# Sheet1.net
KiCad netlist of a schematic drawn in Altium Designer
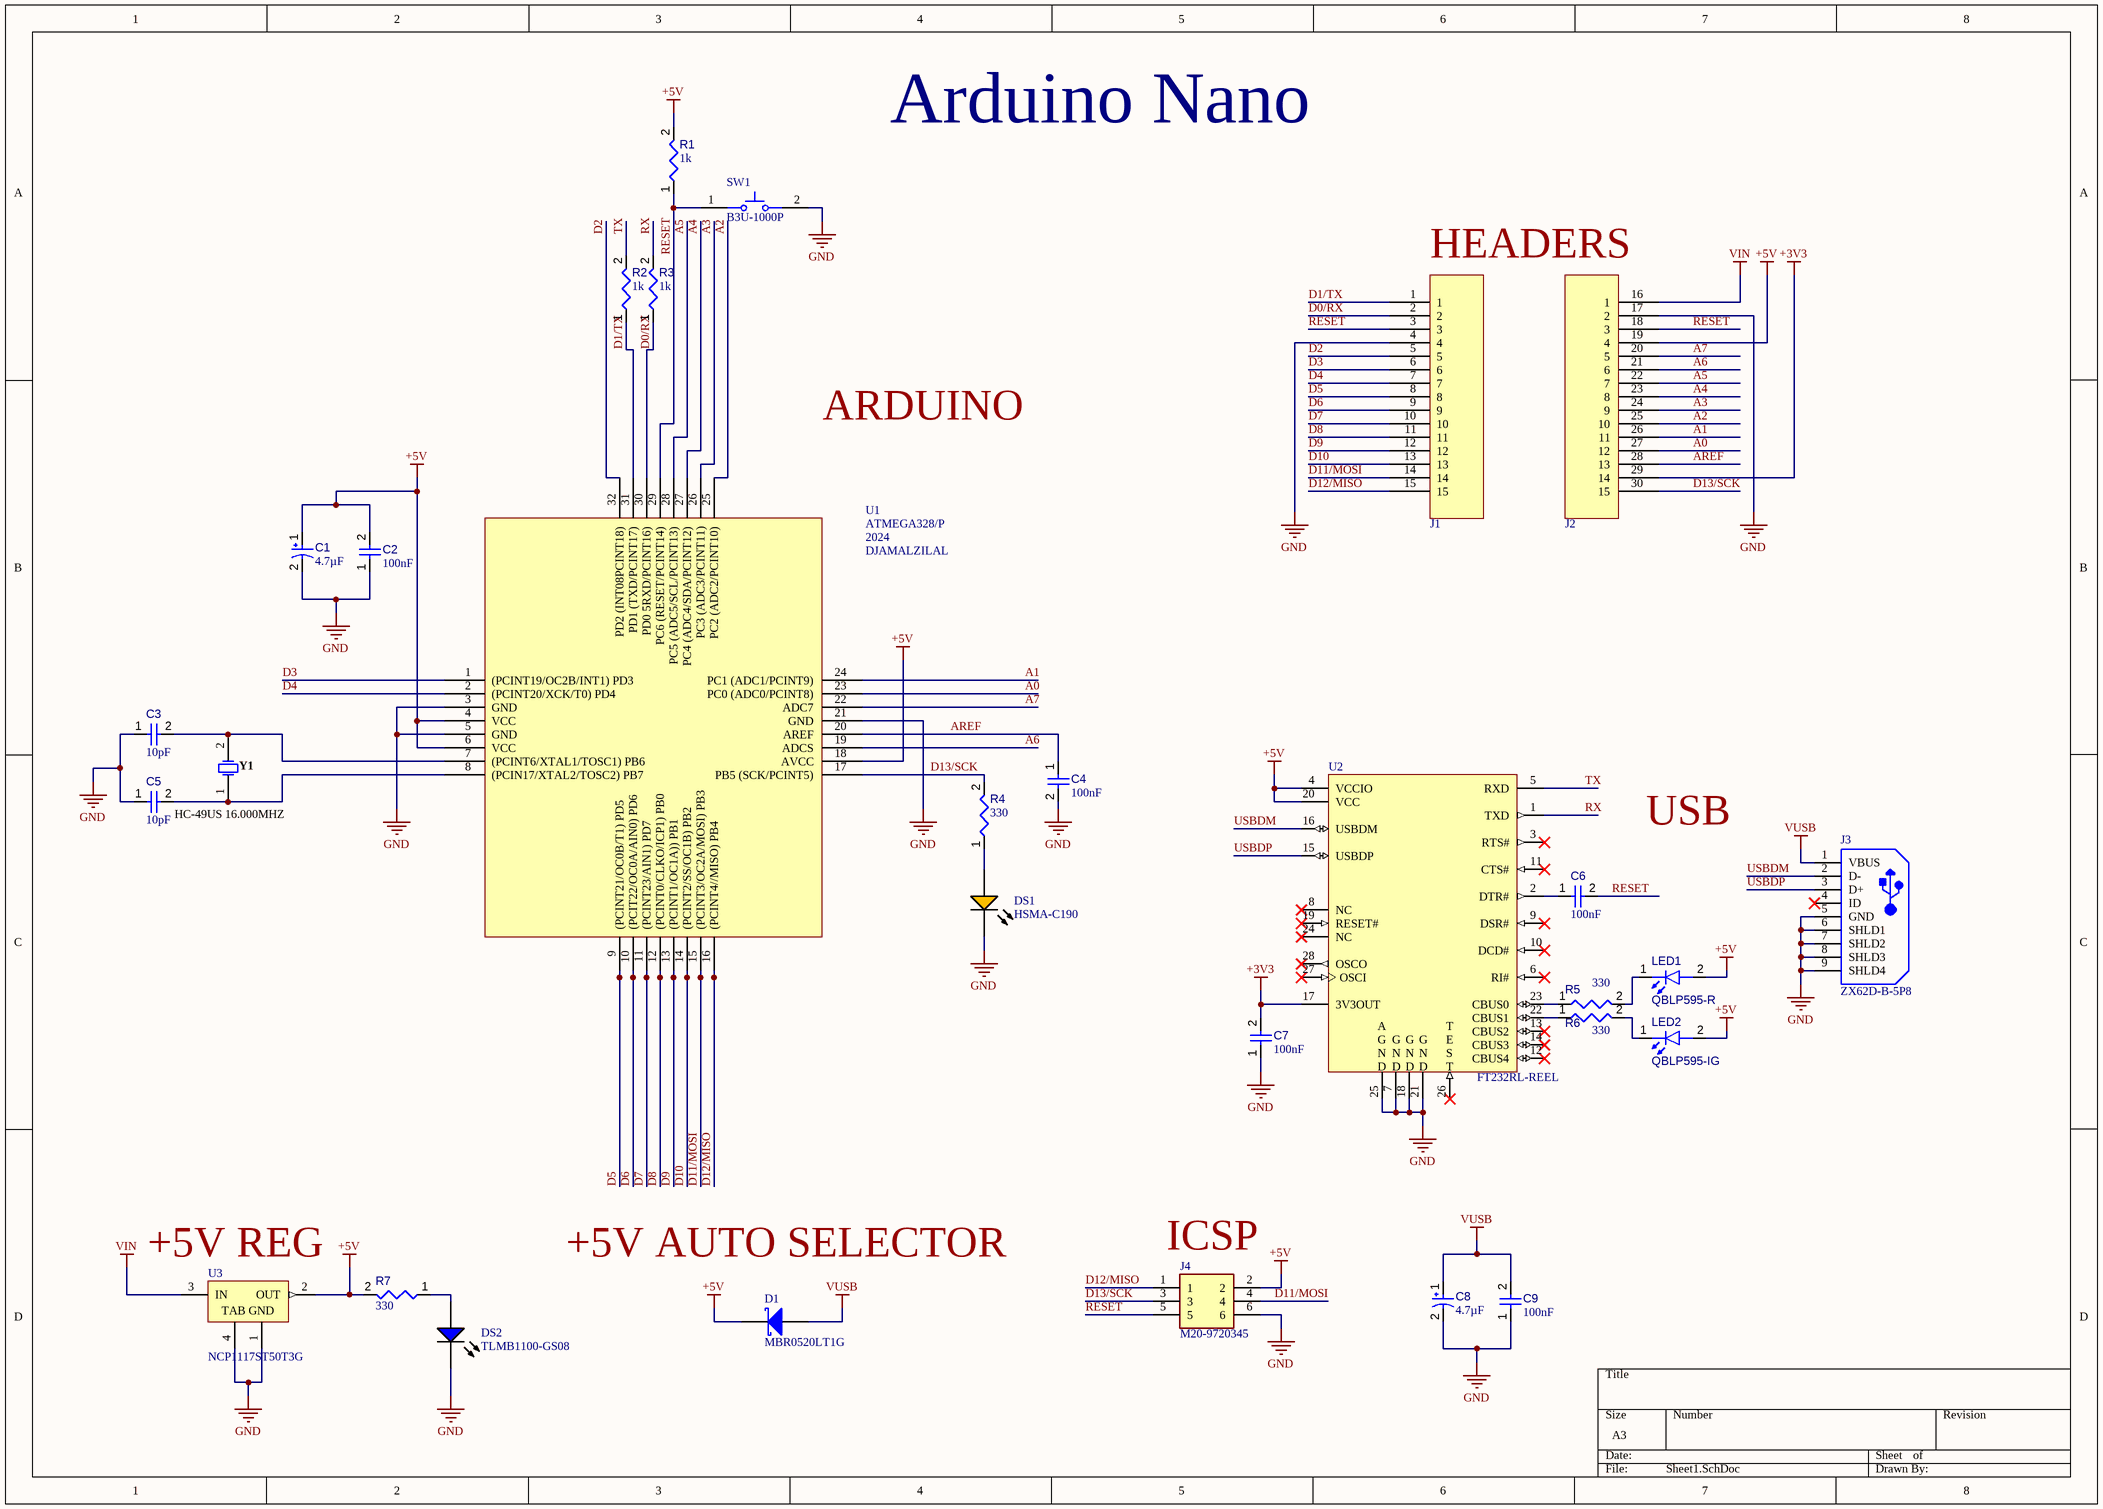
[diagram p0: Sheet1.SchDoc]

(export (version "E")
  (design (tool "Eeschema 10.0.6"))
  (components
    (comp (ref "C1")
      (value "4.7µF")
      (footprint "CAPPR55-200-1100X500X1200")
      (description "Aluminum Electrolytic Capacitor, 4.7 uF, +/- 20%, 50 V, -40 to 85 degC, 2-Pin THD, RoHS, Bulk")
      (fields (field (name "MANUFACTURER") "Panasonic") (field (name "TOLERANCE") "20%"))
      (libsource (lib "Paris - Saclay University") (part "CAP-P-2"))
    )
    (comp (ref "C2")
      (value "100nF")
      (footprint "CAPC1005X56X25LL10T15")
      (description "Chip Capacitor, 0.1 uF, +/- 5%, 16 V, 0402 (1005 Metric)")
      (fields (field (name "TOLERANCE") "5%") (field (name "Comment") "Capacitor 0.1 uF +/- 5% 16 V 0402"))
      (libsource (lib "Paris - Saclay University") (part "CAP-NP-2"))
    )
    (comp (ref "C3")
      (value "10pF")
      (footprint "CAPC1005X55X30LL05T10")
      (description "Chip Capacitor, 10 pF, +/- 0.25 pF, 50 V, 0402 (1005 Metric)")
      (fields
        (field (name "TOLERANCE") "0.25%")
        (field (name "Comment") "Capacitor 10 pF +/- 0.25 pF 50 V 0402")
      )
      (libsource (lib "Paris - Saclay University") (part "CAP-NP-2"))
    )
    (comp (ref "C4")
      (value "100nF")
      (footprint "CAPC1005X56X25LL10T15")
      (description "Chip Capacitor, 0.1 uF, +/- 5%, 16 V, 0402 (1005 Metric)")
      (fields (field (name "TOLERANCE") "5%") (field (name "Comment") "Capacitor 0.1 uF +/- 5% 16 V 0402"))
      (libsource (lib "Paris - Saclay University") (part "CAP-NP-2"))
    )
    (comp (ref "C5")
      (value "10pF")
      (footprint "CAPC1005X55X30LL05T10")
      (description "Chip Capacitor, 10 pF, +/- 0.25 pF, 50 V, 0402 (1005 Metric)")
      (fields
        (field (name "TOLERANCE") "0.25%")
        (field (name "Comment") "Capacitor 10 pF +/- 0.25 pF 50 V 0402")
      )
      (libsource (lib "Paris - Saclay University") (part "CAP-NP-2"))
    )
    (comp (ref "C6")
      (value "100nF")
      (footprint "CAPC1005X56X25LL10T15")
      (description "Chip Capacitor, 0.1 uF, +/- 5%, 16 V, 0402 (1005 Metric)")
      (fields (field (name "TOLERANCE") "5%") (field (name "Comment") "Capacitor 0.1 uF +/- 5% 16 V 0402"))
      (libsource (lib "Paris - Saclay University") (part "CAP-NP-2"))
    )
    (comp (ref "C7")
      (value "100nF")
      (footprint "CAPC1005X56X25LL10T15")
      (description "Chip Capacitor, 0.1 uF, +/- 5%, 16 V, 0402 (1005 Metric)")
      (fields (field (name "TOLERANCE") "5%") (field (name "Comment") "Capacitor 0.1 uF +/- 5% 16 V 0402"))
      (libsource (lib "Paris - Saclay University") (part "CAP-NP-2"))
    )
    (comp (ref "C8")
      (value "4.7µF")
      (footprint "CAPPR55-200-1100X500X1200")
      (description "Aluminum Electrolytic Capacitor, 4.7 uF, +/- 20%, 50 V, -40 to 85 degC, 2-Pin THD, RoHS, Bulk")
      (fields (field (name "MANUFACTURER") "Panasonic") (field (name "TOLERANCE") "20%"))
      (libsource (lib "Paris - Saclay University") (part "CAP-P-2"))
    )
    (comp (ref "C9")
      (value "100nF")
      (footprint "CAPC1005X56X25LL10T15")
      (description "Chip Capacitor, 0.1 uF, +/- 5%, 16 V, 0402 (1005 Metric)")
      (fields (field (name "TOLERANCE") "5%") (field (name "Comment") "Capacitor 0.1 uF +/- 5% 16 V 0402"))
      (libsource (lib "Paris - Saclay University") (part "CAP-NP-2"))
    )
    (comp (ref "D1")
      (value "MBR0520LT1G")
      (footprint "ONSC-SOD-123-2-425-04_V")
      (description "Schottky Power Rectifier, 20 V, 5.5 A, -65 to 125 degC, 2-Pin SMD, RoHS, Tape and Reel")
      (fields (field (name "MANUFACTURER") "ON Semiconductor"))
      (libsource (lib "Paris - Saclay University") (part "DSKY-AK-2"))
    )
    (comp (ref "DS1")
      (value "HSMA-C190")
      (footprint "AVAG-HSMX-C190_V")
      (description "LED Uni-Color Amber, 60 mW, 20 mA, -40 to 85 degC, 2-Pin SMD, RoHS, Tape and Reel")
      (fields (field (name "POWER") "60mW") (field (name "MANUFACTURER") "Avago"))
      (libsource (lib "Paris - Saclay University") (part "LED-AMBER-AK-2"))
    )
    (comp (ref "DS2")
      (value "TLMB1100-GS08")
      (footprint "VISH-TLMX1100-2_V")
      (description "Blue LED, 10 mA, 3.9 V, -40 to 100 degC, 2-Pin SMD (0603), RoHS, Tape and Reel")
      (fields (field (name "POWER") "68mW") (field (name "MANUFACTURER") "Vishay Semiconductor"))
      (libsource (lib "Paris - Saclay University") (part "LED-BLUE-AK-2"))
    )
    (comp (ref "J1")
      (value "both parts are inseparated")
      (footprint "PCBComponent_1")
      (libsource (lib "Integrated_Library_Header_15") (part "Header 15"))
    )
    (comp (ref "J2")
      (value "both parts are inseparated")
      (footprint "PCBComponent_1")
      (libsource (lib "") (part "Header 15_1"))
    )
    (comp (ref "J3")
      (value "ZX62D-B-5P8")
      (footprint "HIRO-ZX62D-B-5P8_V")
      (fields (field (name "MANUFACTURER") "Hirose Electric"))
      (libsource (lib "Paris - Saclay University") (part "USB-5-4SHLD"))
    )
    (comp (ref "J4")
      (value "M20-9720345")
      (footprint "SamacSys:HDRV6W64P254_2X3_762X508X864P")
      (description "Connector")
      (fields (field (name "MOUSER PART NUMBER") "855-M20-9720345"))
      (libsource (lib "*") (part "M20-9720345"))
    )
    (comp (ref "LED1")
      (value "QBLP595-R")
      (footprint "QTB-QBLP595_V")
      (description "Chip LED 0402, Red, 0.02 A, 2.0 to 2.5 V, -40 to 80 degC, 2-Pin SMD, RoHS, Tape and Reel")
      (libsource (lib "Paris - Saclay University") (part "LED-KA-2"))
    )
    (comp (ref "LED2")
      (value "QBLP595-IG")
      (footprint "QTB-QBLP595_V")
      (description "Chip LED 0402, Green, 0.02 A, 3.1 to 3.7 V, -40 to 80 degC, 2-Pin SMD, RoHS, Tape and Reel")
      (libsource (lib "Paris - Saclay University") (part "LED-KA-2"))
    )
    (comp (ref "R1")
      (value "1k")
      (footprint "RESC0402(1005)_L")
      (description "1K 0.063W 5% 0402 (1005 Metric)  SMD")
      (fields (field (name "POWER") "63mW") (field (name "TOLERANCE") "5%"))
      (libsource (lib "Paris - Saclay University") (part "1KR2J"))
    )
    (comp (ref "R2")
      (value "1k")
      (footprint "RESC0402(1005)_L")
      (description "1K 0.063W 5% 0402 (1005 Metric)  SMD")
      (fields (field (name "POWER") "63mW") (field (name "TOLERANCE") "5%"))
      (libsource (lib "Paris - Saclay University") (part "1KR2J"))
    )
    (comp (ref "R3")
      (value "1k")
      (footprint "RESC0402(1005)_L")
      (description "1K 0.063W 5% 0402 (1005 Metric)  SMD")
      (fields (field (name "POWER") "63mW") (field (name "TOLERANCE") "5%"))
      (libsource (lib "Paris - Saclay University") (part "1KR2J"))
    )
    (comp (ref "R4")
      (value "330")
      (footprint "RESC0402(1005)_L")
      (description "330R 0.063W 5% 0402 (1005 Metric)  SMD")
      (fields (field (name "TOLERANCE") "5%") (field (name "POWER") "63mW"))
      (libsource (lib "Paris - Saclay University") (part "330R2J"))
    )
    (comp (ref "R5")
      (value "330")
      (footprint "RESC0402(1005)_L")
      (description "330R 0.063W 5% 0402 (1005 Metric)  SMD")
      (fields (field (name "TOLERANCE") "5%") (field (name "POWER") "63mW"))
      (libsource (lib "Paris - Saclay University") (part "330R2J"))
    )
    (comp (ref "R6")
      (value "330")
      (footprint "RESC0402(1005)_L")
      (description "330R 0.063W 5% 0402 (1005 Metric)  SMD")
      (fields (field (name "TOLERANCE") "5%") (field (name "POWER") "63mW"))
      (libsource (lib "Paris - Saclay University") (part "330R2J"))
    )
    (comp (ref "R7")
      (value "330")
      (footprint "RESC0402(1005)_L")
      (description "330R 0.063W 5% 0402 (1005 Metric)  SMD")
      (fields (field (name "TOLERANCE") "5%") (field (name "POWER") "63mW"))
      (libsource (lib "Paris - Saclay University") (part "330R2J"))
    )
    (comp (ref "SW1")
      (value "B3U-1000P")
      (footprint "OMRON-B3U-1000_V")
      (description "Tactile Switch, SPST-NO, 0.05 A, 12 V, -25 to 70 degC, 2-Pin SMD, RoHS, Tape and Reel")
      (fields (field (name "MANUFACTURER") "Omron Electronic Components"))
      (libsource (lib "Paris - Saclay University") (part "SW-SPST-NO-2"))
    )
    (comp (ref "U1")
      (value "ATMEGA328/P")
      (footprint "ATMEGA328/P")
      (fields (field (name "DATA CREATED") "2024") (field (name "CREATED BY") "DJAMALZILAL"))
      (libsource (lib "Integrated_Library_ATmega328p") (part "ATMEGA328/P"))
    )
    (comp (ref "U2")
      (value "FT232RL-REEL")
      (footprint "FTDI-SSOP-28_M")
      (description "USB UART IC, -0.5 to 6 V, 24 mA, -40 to 85 degC, 28-Pin SSOP, RoHS, Tape and Reel")
      (fields (field (name "MANUFACTURER") "Future Technology Devices International (FTDI)"))
      (libsource (lib "Paris - Saclay University") (part "FTDI-FT232-SSOP-28"))
    )
    (comp (ref "U3")
      (value "NCP1117ST50T3G")
      (footprint "ONSC-SOT-223-4-318H-01_A_V")
      (fields (field (name "MANUFACTURER") "ON Semiconductor"))
      (libsource (lib "Paris - Saclay University") (part "ONSC-NCP1117ST-TO-223-4"))
    )
    (comp (ref "Y1")
      (value "HC-49US 16.000MHZ")
      (footprint "JPY-HC-49US")
      (description "Crystal, 16 MHz, +/- 30 ppm, 18 pF, -20 to 70 degC, 2-Pin THD")
      (fields (field (name "MANUFACTURER") "Jing peng yuan"))
      (libsource (lib "Paris - Saclay University") (part "XTAL-1-2-2"))
    )
  )
  (nets
    (net (code "1") (name "+3V3") (class "Default")
      (node (ref "C7") (pin "2") (pinfunction "2_2") (pintype "passive"))
      (node (ref "J2") (pin "29") (pinfunction "14_29") (pintype "passive"))
      (node (ref "U2") (pin "17") (pinfunction "3V3OUT_17") (pintype "power_in"))
    )
    (net (code "2") (name "+5V") (class "Default")
      (node (ref "C1") (pin "1") (pinfunction "1_1") (pintype "passive"))
      (node (ref "C2") (pin "2") (pinfunction "2_2") (pintype "passive"))
      (node (ref "D1") (pin "2") (pinfunction "K_2") (pintype "passive"))
      (node (ref "J2") (pin "19") (pinfunction "4_19") (pintype "passive"))
      (node (ref "J4") (pin "2") (pinfunction "2_2") (pintype "passive"))
      (node (ref "LED1") (pin "2") (pinfunction "A_2") (pintype "passive"))
      (node (ref "LED2") (pin "2") (pinfunction "A_2") (pintype "passive"))
      (node (ref "R1") (pin "2") (pinfunction "2_2") (pintype "passive"))
      (node (ref "R7") (pin "2") (pinfunction "2_2") (pintype "passive"))
      (node (ref "U1") (pin "18") (pinfunction "AVCC_18") (pintype "passive"))
      (node (ref "U1") (pin "4") (pinfunction "VCC_4") (pintype "passive"))
      (node (ref "U1") (pin "6") (pinfunction "VCC_6") (pintype "passive"))
      (node (ref "U2") (pin "20") (pinfunction "VCC_20") (pintype "passive"))
      (node (ref "U2") (pin "4") (pinfunction "VCCIO_4") (pintype "passive"))
      (node (ref "U3") (pin "2") (pinfunction "OUT_2") (pintype "output"))
    )
    (net (code "3") (name "/A0") (class "Default")
      (node (ref "J2") (pin "27") (pinfunction "12_27") (pintype "passive"))
      (node (ref "U1") (pin "23") (pinfunction "PC0_(ADC0/PCINT8)_23") (pintype "passive"))
    )
    (net (code "4") (name "/A1") (class "Default")
      (node (ref "J2") (pin "26") (pinfunction "11_26") (pintype "passive"))
      (node (ref "U1") (pin "24") (pinfunction "PC1_(ADC1/PCINT9)_24") (pintype "passive"))
    )
    (net (code "5") (name "/A2") (class "Default")
      (node (ref "J2") (pin "25") (pinfunction "10_25") (pintype "passive"))
      (node (ref "U1") (pin "25") (pinfunction "PC2_(ADC2/PCINT10)_25") (pintype "passive"))
    )
    (net (code "6") (name "/A3") (class "Default")
      (node (ref "J2") (pin "24") (pinfunction "9_24") (pintype "passive"))
      (node (ref "U1") (pin "26") (pinfunction "PC3_(ADC3/PCINT11)_26") (pintype "passive"))
    )
    (net (code "7") (name "/A4") (class "Default")
      (node (ref "J2") (pin "23") (pinfunction "8_23") (pintype "passive"))
      (node (ref "U1") (pin "27") (pinfunction "PC4_(ADC4/SDA/PCINT12)_27") (pintype "passive"))
    )
    (net (code "8") (name "/A5") (class "Default")
      (node (ref "J2") (pin "22") (pinfunction "7_22") (pintype "passive"))
      (node (ref "U1") (pin "28") (pinfunction "PC5_(ADC5/SCL/PCINT13)_28") (pintype "passive"))
    )
    (net (code "9") (name "/A6") (class "Default")
      (node (ref "J2") (pin "21") (pinfunction "6_21") (pintype "passive"))
      (node (ref "U1") (pin "19") (pinfunction "ADCS_19") (pintype "passive"))
    )
    (net (code "10") (name "/A7") (class "Default")
      (node (ref "J2") (pin "20") (pinfunction "5_20") (pintype "passive"))
      (node (ref "U1") (pin "22") (pinfunction "ADC7_22") (pintype "passive"))
    )
    (net (code "11") (name "/AREF") (class "Default")
      (node (ref "C4") (pin "1") (pinfunction "1_1") (pintype "passive"))
      (node (ref "J2") (pin "28") (pinfunction "13_28") (pintype "passive"))
      (node (ref "U1") (pin "20") (pinfunction "AREF_20") (pintype "passive"))
    )
    (net (code "12") (name "/D0{slash}RX") (class "Default")
      (node (ref "J1") (pin "2") (pinfunction "2_2") (pintype "passive"))
      (node (ref "R3") (pin "1") (pinfunction "1_1") (pintype "passive"))
      (node (ref "U1") (pin "30") (pinfunction "PD0_5RXD/PCINT16)_30") (pintype "passive"))
    )
    (net (code "13") (name "/D1{slash}TX") (class "Default")
      (node (ref "J1") (pin "1") (pinfunction "1_1") (pintype "passive"))
      (node (ref "R2") (pin "1") (pinfunction "1_1") (pintype "passive"))
      (node (ref "U1") (pin "31") (pinfunction "PD1_(TXD/PCINT17)_31") (pintype "passive"))
    )
    (net (code "14") (name "/D2") (class "Default")
      (node (ref "J1") (pin "5") (pinfunction "5_5") (pintype "passive"))
      (node (ref "U1") (pin "32") (pinfunction "PD2_(INT08PCINT18)_32") (pintype "passive"))
    )
    (net (code "15") (name "/D3") (class "Default")
      (node (ref "J1") (pin "6") (pinfunction "6_6") (pintype "passive"))
      (node (ref "U1") (pin "1") (pinfunction "(PCINT19/OC2B/INT1)_PD3_1") (pintype "passive"))
    )
    (net (code "16") (name "/D4") (class "Default")
      (node (ref "J1") (pin "7") (pinfunction "7_7") (pintype "passive"))
      (node (ref "U1") (pin "2") (pinfunction "(PCINT20/XCK/T0)_PD4_2") (pintype "passive"))
    )
    (net (code "17") (name "/D5") (class "Default")
      (node (ref "J1") (pin "8") (pinfunction "8_8") (pintype "passive"))
      (node (ref "U1") (pin "9") (pinfunction "(PCINT21/OC0B/T1)_PD5_9") (pintype "passive"))
    )
    (net (code "18") (name "/D6") (class "Default")
      (node (ref "J1") (pin "9") (pinfunction "9_9") (pintype "passive"))
      (node (ref "U1") (pin "10") (pinfunction "(PCIT22/OC0A/AIN0)_PD6_10") (pintype "passive"))
    )
    (net (code "19") (name "/D7") (class "Default")
      (node (ref "J1") (pin "10") (pinfunction "10_10") (pintype "passive"))
      (node (ref "U1") (pin "11") (pinfunction "(PCINT23/AIN1)_PD7_11") (pintype "passive"))
    )
    (net (code "20") (name "/D8") (class "Default")
      (node (ref "J1") (pin "11") (pinfunction "11_11") (pintype "passive"))
      (node (ref "U1") (pin "12") (pinfunction "(PCINT0/CLKO/ICP1)_PB0_12") (pintype "passive"))
    )
    (net (code "21") (name "/D9") (class "Default")
      (node (ref "J1") (pin "12") (pinfunction "12_12") (pintype "passive"))
      (node (ref "U1") (pin "13") (pinfunction "(PCINT1/OC1A))_PB1_13") (pintype "passive"))
    )
    (net (code "22") (name "/D10") (class "Default")
      (node (ref "J1") (pin "13") (pinfunction "13_13") (pintype "passive"))
      (node (ref "U1") (pin "14") (pinfunction "(PCINT2/SS/OC1B)_PB2_14") (pintype "passive"))
    )
    (net (code "23") (name "/D11{slash}MOSI") (class "Default")
      (node (ref "J1") (pin "14") (pinfunction "14_14") (pintype "passive"))
      (node (ref "J4") (pin "4") (pinfunction "4_4") (pintype "passive"))
      (node (ref "U1") (pin "15") (pinfunction "(PCINT3/OC2A/MOSI)_PB3_15") (pintype "passive"))
    )
    (net (code "24") (name "/D12{slash}MISO") (class "Default")
      (node (ref "J1") (pin "15") (pinfunction "15_15") (pintype "passive"))
      (node (ref "J4") (pin "1") (pinfunction "1_1") (pintype "passive"))
      (node (ref "U1") (pin "16") (pinfunction "(PCINT4//MISO)_PB4_16") (pintype "passive"))
    )
    (net (code "25") (name "/D13{slash}SCK") (class "Default")
      (node (ref "J2") (pin "30") (pinfunction "15_30") (pintype "passive"))
      (node (ref "J4") (pin "3") (pinfunction "3_3") (pintype "passive"))
      (node (ref "R4") (pin "2") (pinfunction "2_2") (pintype "passive"))
      (node (ref "U1") (pin "17") (pinfunction "PB5_(SCK/PCINT5)_17") (pintype "passive"))
    )
    (net (code "26") (name "/RESET") (class "Default")
      (node (ref "C6") (pin "2") (pinfunction "2_2") (pintype "passive"))
      (node (ref "J1") (pin "3") (pinfunction "3_3") (pintype "passive"))
      (node (ref "J2") (pin "18") (pinfunction "3_18") (pintype "passive"))
      (node (ref "J4") (pin "5") (pinfunction "5_5") (pintype "passive"))
      (node (ref "R1") (pin "1") (pinfunction "1_1") (pintype "passive"))
      (node (ref "SW1") (pin "1") (pinfunction "1_1") (pintype "passive"))
      (node (ref "U1") (pin "29") (pinfunction "PC6_(RESET/PCINT14)_29") (pintype "passive"))
    )
    (net (code "27") (name "/RX") (class "Default")
      (node (ref "R3") (pin "2") (pinfunction "2_2") (pintype "passive"))
      (node (ref "U2") (pin "1") (pinfunction "TXD_1") (pintype "output"))
    )
    (net (code "28") (name "/TX") (class "Default")
      (node (ref "R2") (pin "2") (pinfunction "2_2") (pintype "passive"))
      (node (ref "U2") (pin "5") (pinfunction "RXD_5") (pintype "passive"))
    )
    (net (code "29") (name "/USBDM") (class "Default")
      (node (ref "J3") (pin "2") (pinfunction "D-_2") (pintype "passive"))
      (node (ref "U2") (pin "16") (pinfunction "USBDM_16") (pintype "bidirectional"))
    )
    (net (code "30") (name "/USBDP") (class "Default")
      (node (ref "J3") (pin "3") (pinfunction "D+_3") (pintype "passive"))
      (node (ref "U2") (pin "15") (pinfunction "USBDP_15") (pintype "bidirectional"))
    )
    (net (code "31") (name "GND") (class "Default")
      (node (ref "C1") (pin "2") (pinfunction "2_2") (pintype "passive"))
      (node (ref "C2") (pin "1") (pinfunction "1_1") (pintype "passive"))
      (node (ref "C3") (pin "1") (pinfunction "1_1") (pintype "passive"))
      (node (ref "C4") (pin "2") (pinfunction "2_2") (pintype "passive"))
      (node (ref "C5") (pin "1") (pinfunction "1_1") (pintype "passive"))
      (node (ref "C7") (pin "1") (pinfunction "1_1") (pintype "passive"))
      (node (ref "C8") (pin "2") (pinfunction "2_2") (pintype "passive"))
      (node (ref "C9") (pin "1") (pinfunction "1_1") (pintype "passive"))
      (node (ref "DS1") (pin "2") (pinfunction "K_2") (pintype "passive"))
      (node (ref "DS2") (pin "2") (pinfunction "K_2") (pintype "passive"))
      (node (ref "J1") (pin "4") (pinfunction "4_4") (pintype "passive"))
      (node (ref "J2") (pin "17") (pinfunction "2_17") (pintype "passive"))
      (node (ref "J3") (pin "5") (pinfunction "GND_5") (pintype "passive"))
      (node (ref "J3") (pin "6") (pinfunction "SHLD1_6") (pintype "passive"))
      (node (ref "J3") (pin "7") (pinfunction "SHLD2_7") (pintype "passive"))
      (node (ref "J3") (pin "8") (pinfunction "SHLD3_8") (pintype "passive"))
      (node (ref "J3") (pin "9") (pinfunction "SHLD4_9") (pintype "passive"))
      (node (ref "J4") (pin "6") (pinfunction "6_6") (pintype "passive"))
      (node (ref "SW1") (pin "2") (pinfunction "2_2") (pintype "passive"))
      (node (ref "U1") (pin "21") (pinfunction "GND_21") (pintype "passive"))
      (node (ref "U1") (pin "3") (pinfunction "GND_3") (pintype "passive"))
      (node (ref "U1") (pin "5") (pinfunction "GND_5") (pintype "passive"))
      (node (ref "U2") (pin "18") (pinfunction "GND_18") (pintype "power_in"))
      (node (ref "U2") (pin "21") (pinfunction "GND_21") (pintype "power_in"))
      (node (ref "U2") (pin "25") (pinfunction "AGND_25") (pintype "power_in"))
      (node (ref "U2") (pin "7") (pinfunction "GND_7") (pintype "power_in"))
      (node (ref "U3") (pin "1") (pinfunction "GND_1") (pintype "power_in"))
      (node (ref "U3") (pin "4") (pinfunction "TAB_4") (pintype "power_in"))
    )
    (net (code "32") (name "Net-(DS1-A)") (class "Default")
      (node (ref "DS1") (pin "1") (pinfunction "A_1") (pintype "passive"))
      (node (ref "R4") (pin "1") (pinfunction "1_1") (pintype "passive"))
    )
    (net (code "33") (name "Net-(DS2-A)") (class "Default")
      (node (ref "DS2") (pin "1") (pinfunction "A_1") (pintype "passive"))
      (node (ref "R7") (pin "1") (pinfunction "1_1") (pintype "passive"))
    )
    (net (code "34") (name "Net-(LED1-K)") (class "Default")
      (node (ref "LED1") (pin "1") (pinfunction "K_1") (pintype "passive"))
      (node (ref "R5") (pin "2") (pinfunction "2_2") (pintype "passive"))
    )
    (net (code "35") (name "Net-(LED2-K)") (class "Default")
      (node (ref "LED2") (pin "1") (pinfunction "K_1") (pintype "passive"))
      (node (ref "R6") (pin "2") (pinfunction "2_2") (pintype "passive"))
    )
    (net (code "36") (name "Net-(U1-(PCIN17{slash}XTAL2{slash}TOSC2)_PB7)") (class "Default")
      (node (ref "C5") (pin "2") (pinfunction "2_2") (pintype "passive"))
      (node (ref "U1") (pin "8") (pinfunction "(PCIN17/XTAL2/TOSC2)_PB7_8") (pintype "passive"))
      (node (ref "Y1") (pin "1") (pinfunction "1_1") (pintype "passive"))
    )
    (net (code "37") (name "Net-(U1-(PCINT6{slash}XTAL1{slash}TOSC1)_PB6)") (class "Default")
      (node (ref "C3") (pin "2") (pinfunction "2_2") (pintype "passive"))
      (node (ref "U1") (pin "7") (pinfunction "(PCINT6/XTAL1/TOSC1)_PB6_7") (pintype "passive"))
      (node (ref "Y1") (pin "2") (pinfunction "2_2") (pintype "passive"))
    )
    (net (code "38") (name "Net-(U2-CBUS0)") (class "Default")
      (node (ref "R5") (pin "1") (pinfunction "1_1") (pintype "passive"))
      (node (ref "U2") (pin "23") (pinfunction "CBUS0_23") (pintype "bidirectional"))
    )
    (net (code "39") (name "Net-(U2-CBUS1)") (class "Default")
      (node (ref "R6") (pin "1") (pinfunction "1_1") (pintype "passive"))
      (node (ref "U2") (pin "22") (pinfunction "CBUS1_22") (pintype "bidirectional"))
    )
    (net (code "40") (name "Net-(U2-DTR#)") (class "Default")
      (node (ref "C6") (pin "1") (pinfunction "1_1") (pintype "passive"))
      (node (ref "U2") (pin "2") (pinfunction "DTR#_2") (pintype "output"))
    )
    (net (code "41") (name "VIN") (class "Default")
      (node (ref "J2") (pin "16") (pinfunction "1_16") (pintype "passive"))
      (node (ref "U3") (pin "3") (pinfunction "IN_3") (pintype "passive"))
    )
    (net (code "42") (name "VUSB") (class "Default")
      (node (ref "C8") (pin "1") (pinfunction "1_1") (pintype "passive"))
      (node (ref "C9") (pin "2") (pinfunction "2_2") (pintype "passive"))
      (node (ref "D1") (pin "1") (pinfunction "A_1") (pintype "passive"))
      (node (ref "J3") (pin "1") (pinfunction "VBUS_1") (pintype "passive"))
    )
    (net (code "43") (name "unconnected-(J3-ID-Pad4)") (class "Default")
      (node (ref "J3") (pin "4") (pinfunction "ID_4") (pintype "passive+no_connect"))
    )
    (net (code "44") (name "unconnected-(U2-CBUS2-Pad13)") (class "Default")
      (node (ref "U2") (pin "13") (pinfunction "CBUS2_13") (pintype "bidirectional+no_connect"))
    )
    (net (code "45") (name "unconnected-(U2-CBUS3-Pad14)") (class "Default")
      (node (ref "U2") (pin "14") (pinfunction "CBUS3_14") (pintype "bidirectional+no_connect"))
    )
    (net (code "46") (name "unconnected-(U2-CBUS4-Pad12)") (class "Default")
      (node (ref "U2") (pin "12") (pinfunction "CBUS4_12") (pintype "bidirectional+no_connect"))
    )
    (net (code "47") (name "unconnected-(U2-CTS#-Pad11)") (class "Default")
      (node (ref "U2") (pin "11") (pinfunction "CTS#_11") (pintype "input+no_connect"))
    )
    (net (code "48") (name "unconnected-(U2-DCD#-Pad10)") (class "Default")
      (node (ref "U2") (pin "10") (pinfunction "DCD#_10") (pintype "input+no_connect"))
    )
    (net (code "49") (name "unconnected-(U2-DSR#-Pad9)") (class "Default")
      (node (ref "U2") (pin "9") (pinfunction "DSR#_9") (pintype "input+no_connect"))
    )
    (net (code "50") (name "unconnected-(U2-NC-Pad8)") (class "Default")
      (node (ref "U2") (pin "8") (pinfunction "NC_8") (pintype "passive+no_connect"))
    )
    (net (code "51") (name "unconnected-(U2-NC-Pad24)") (class "Default")
      (node (ref "U2") (pin "24") (pinfunction "NC_24") (pintype "passive+no_connect"))
    )
    (net (code "52") (name "unconnected-(U2-OSCI-Pad27)") (class "Default")
      (node (ref "U2") (pin "27") (pinfunction "OSCI_27") (pintype "input+no_connect"))
    )
    (net (code "53") (name "unconnected-(U2-OSCO-Pad28)") (class "Default")
      (node (ref "U2") (pin "28") (pinfunction "OSCO_28") (pintype "output+no_connect"))
    )
    (net (code "54") (name "unconnected-(U2-RESET#-Pad19)") (class "Default")
      (node (ref "U2") (pin "19") (pinfunction "RESET#_19") (pintype "input+no_connect"))
    )
    (net (code "55") (name "unconnected-(U2-RI#-Pad6)") (class "Default")
      (node (ref "U2") (pin "6") (pinfunction "RI#_6") (pintype "input+no_connect"))
    )
    (net (code "56") (name "unconnected-(U2-RTS#-Pad3)") (class "Default")
      (node (ref "U2") (pin "3") (pinfunction "RTS#_3") (pintype "output+no_connect"))
    )
    (net (code "57") (name "unconnected-(U2-TEST-Pad26)") (class "Default")
      (node (ref "U2") (pin "26") (pinfunction "TEST_26") (pintype "input+no_connect"))
    )
  )
)
